# Sheet1.net
KiCad netlist of a schematic drawn in Altium Designer
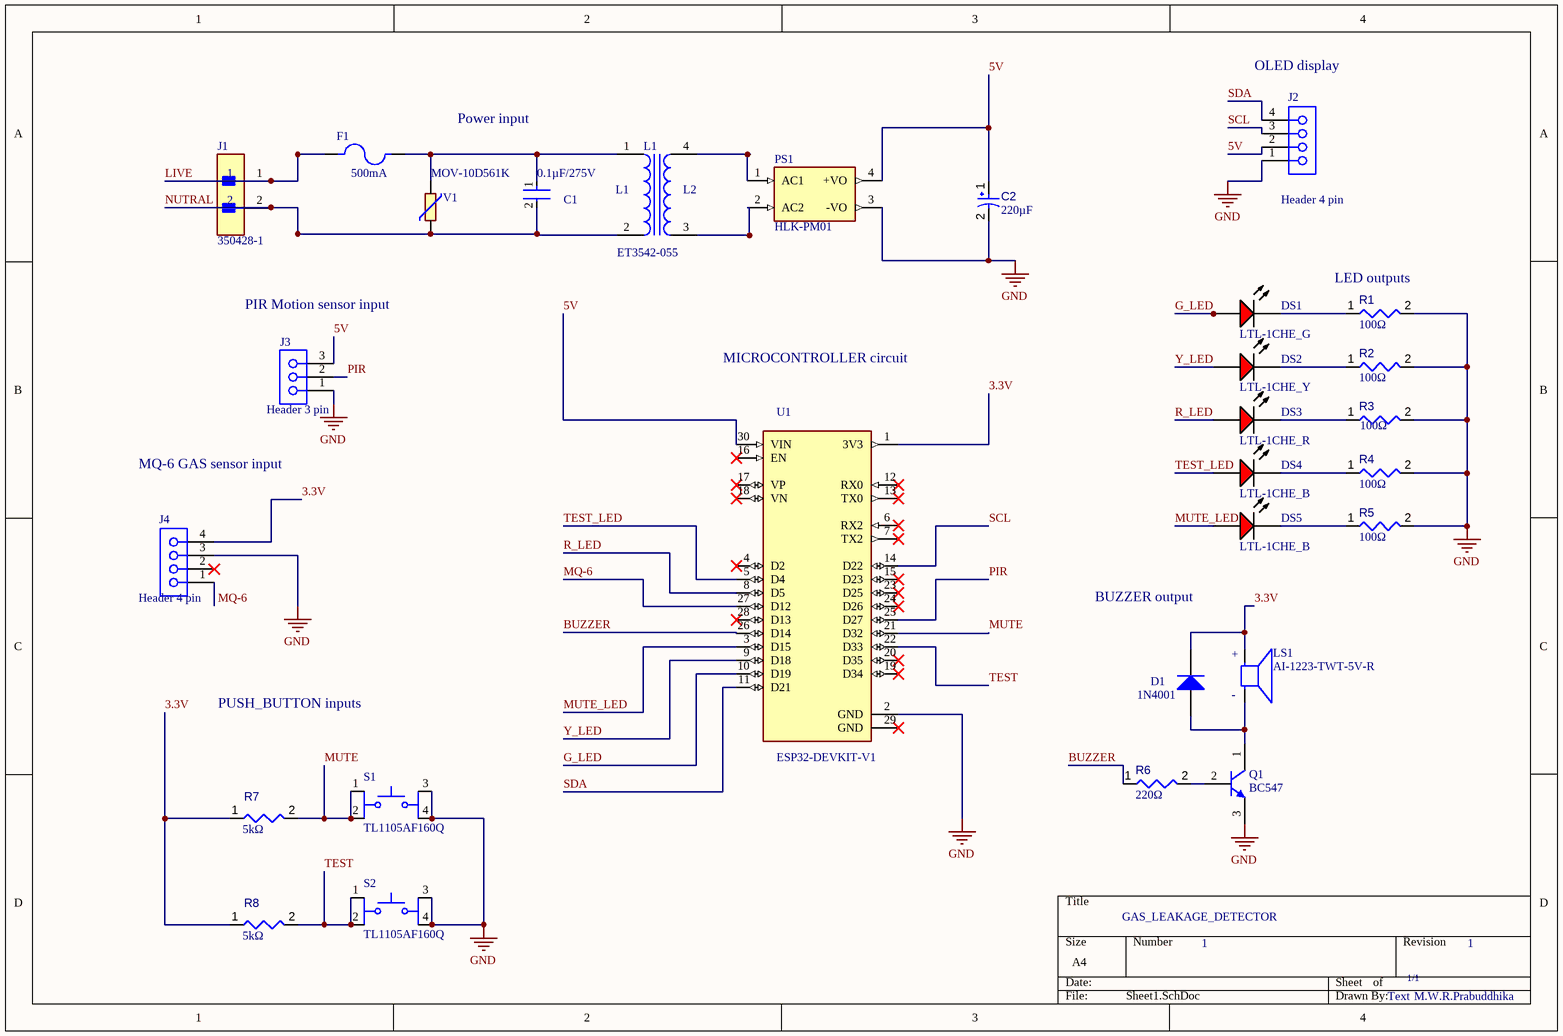
[diagram p0: Sheet1.SchDoc]

(export (version "E")
  (design (tool "Eeschema 10.0.6"))
  (components
    (comp (ref "C1")
      (value "0.1µF/275V")
      (footprint "FP-PMR209MC6100M100R30-MFG")
      (description "FILTER RC 100 OHM/0.1UF TH")
      (fields (field (name "VOLTAGE") "630V") (field (name "TOLERANCE") "20%"))
      (libsource (lib "Altium Content Vault") (part "b4654b650e69147ec39a6b967a45e02"))
    )
    (comp (ref "C2")
      (value "220µF")
      (footprint "CAPPR65-500-1250X1000X1350")
      (description "Aluminum Electrolytic Capacitor, 220 uF, +/- 20%, 50 V, -40 to 85 degC, 2-Pin THD, RoHS, Bulk")
      (fields (field (name "MANUFACTURER") "Panasonic") (field (name "TOLERANCE") "20%"))
      (libsource (lib "University of Moratuwa") (part "CAP-P-2"))
    )
    (comp (ref "D1")
      (value "1N4001")
      (footprint "FAIR-DO-41-2")
      (description "General Purpose Rectifier, 1.1 V, 1.0 A, -55 to 175 degC, 2-Pin DO-41, RoHS, Tape and Reel")
      (fields (field (name "MANUFACTURER") "Fairchild"))
      (libsource (lib "University of Moratuwa") (part "KESE-D_K1A2-2"))
    )
    (comp (ref "DS1")
      (value "LTL-1CHE_G")
      (footprint "INDPR60-254-520X380X650")
      (description "LED Uni-Color Red, 100 mW, 30 mA, -55 to 100 degC, 2-Pin THD, RoHS, Bulk")
      (fields (field (name "MANUFACTURER") "Lite-On"))
      (libsource (lib "University of Moratuwa") (part "LED-RED-AK-2"))
    )
    (comp (ref "DS2")
      (value "LTL-1CHE_Y")
      (footprint "INDPR60-254-520X380X650")
      (description "LED Uni-Color Red, 100 mW, 30 mA, -55 to 100 degC, 2-Pin THD, RoHS, Bulk")
      (fields (field (name "MANUFACTURER") "Lite-On"))
      (libsource (lib "University of Moratuwa") (part "LED-RED-AK-2"))
    )
    (comp (ref "DS3")
      (value "LTL-1CHE_R")
      (footprint "INDPR60-254-520X380X650")
      (description "LED Uni-Color Red, 100 mW, 30 mA, -55 to 100 degC, 2-Pin THD, RoHS, Bulk")
      (fields (field (name "MANUFACTURER") "Lite-On"))
      (libsource (lib "University of Moratuwa") (part "LED-RED-AK-2"))
    )
    (comp (ref "DS4")
      (value "LTL-1CHE_B")
      (footprint "INDPR60-254-520X380X650")
      (description "LED Uni-Color Red, 100 mW, 30 mA, -55 to 100 degC, 2-Pin THD, RoHS, Bulk")
      (fields (field (name "MANUFACTURER") "Lite-On"))
      (libsource (lib "University of Moratuwa") (part "LED-RED-AK-2"))
    )
    (comp (ref "DS5")
      (value "LTL-1CHE_B")
      (footprint "INDPR60-254-520X380X650")
      (description "LED Uni-Color Red, 100 mW, 30 mA, -55 to 100 degC, 2-Pin THD, RoHS, Bulk")
      (fields (field (name "MANUFACTURER") "Lite-On"))
      (libsource (lib "University of Moratuwa") (part "LED-RED-AK-2"))
    )
    (comp (ref "F1")
      (value "500mA")
      (footprint "FUSE_4628")
      (description "5mm Slim Line Fuse holder")
      (fields (field (name "MF") "Keystone") (field (name "MP") "4628"))
      (libsource (lib "University of Moratuwa") (part "4628"))
    )
    (comp (ref "J1")
      (value "350428-1")
      (footprint "FP-350428-1-MFG")
      (description "CONN HEADER VERT 2POS 6.35MM")
      (fields
        (field (name "OCTOPART") "https://octopart.com/350428-1-te+connectivity-46505355")
        (field (name "MANUFACTURER") "TE Connectivity")
      )
      (libsource (lib "Altium Content Vault") (part "3bc925449376181038e59eaffc5286c"))
    )
    (comp (ref "J2")
      (value "OLED display")
      (footprint "SMTC-SLW-104-01-X-S")
      (fields (field (name "MANUFACTURER") "Samtec") (field (name "PARTNUMBER") "SLW-104-01-G-S"))
      (libsource (lib "Altium Content Vault") (part "SMTC-SLW-104-01-X-S"))
    )
    (comp (ref "J3")
      (value "Header 3 pin")
      (footprint "SMTC-SLW-103-01-X-S")
      (fields (field (name "MANUFACTURER") "Samtec") (field (name "PARTNUMBER") "SLW-103-01-G-S"))
      (libsource (lib "Altium Content Vault") (part "SMTC-SLW-103-01-X-S"))
    )
    (comp (ref "J4")
      (value "MQ-6 GAS sensor input")
      (footprint "SMTC-SLW-104-01-X-S")
      (fields (field (name "MANUFACTURER") "Samtec") (field (name "PARTNUMBER") "SLW-104-01-G-S"))
      (libsource (lib "Altium Content Vault") (part "SMTC-SLW-104-01-X-S"))
    )
    (comp (ref "L1")
      (value "ET3542-055")
      (footprint "IND_ET3542-055")
      (description "COMMON MODE CHOKE 10.0mH@2.7Arms")
      (fields (field (name "MF") "Triad Magnetics"))
      (libsource (lib "University of Moratuwa") (part "ET3542-055"))
    )
    (comp (ref "LS1")
      (value "AI-1223-TWT-5V-R")
      (footprint "XDCR_AI-1223-TWT-5V-R")
      (description "ELECTRO MECHANICAL AUDIO INDICATOR")
      (fields (field (name "MF") "PUI Audio,"))
      (libsource (lib "AI-1223-TWT-5V-R") (part "AI-1223-TWT-5V-R"))
    )
    (comp (ref "PS1")
      (value "HLK-PM01")
      (footprint "CONV_HLK-PM01")
      (fields (field (name "MP") "hlk-pm01") (field (name "MF") "Hi-link"))
      (libsource (lib "University of Moratuwa") (part "HLK-PM01"))
    )
    (comp (ref "Q1")
      (value "BC547")
      (footprint "ONSC-TO-92-3-29-11_AM_BL")
      (description "Amplifier Transistor, NPN Silicon, 3-Pin TO-92, Pb-Free, Tape and Reel")
      (fields (field (name "MANUFACTURER") "On Semiconductor") (field (name "PARTNUMBER") "BC547BRL1G"))
      (libsource (lib "Altium Content Vault") (part "ONSC-NPN-C1B2E3-3"))
    )
    (comp (ref "R1")
      (value "100Ω")
      (footprint "RESA60-630X240")
      (description "Axial Resistor, 1 KOhm, +/- 1%, 250 mW, -55 to 155 degC, 2-Pin THD, RoHS, Bulk")
      (fields (field (name "TOLERANCE") "1%") (field (name "POWER") "250mW"))
      (libsource (lib "University of Moratuwa") (part "RES-2"))
    )
    (comp (ref "R2")
      (value "100Ω")
      (footprint "RESA60-630X240")
      (description "Axial Resistor, 1 KOhm, +/- 1%, 250 mW, -55 to 155 degC, 2-Pin THD, RoHS, Bulk")
      (fields (field (name "TOLERANCE") "1%") (field (name "POWER") "250mW"))
      (libsource (lib "University of Moratuwa") (part "RES-2"))
    )
    (comp (ref "R3")
      (value "100Ω")
      (footprint "RESA60-630X240")
      (description "Axial Resistor, 1 KOhm, +/- 1%, 250 mW, -55 to 155 degC, 2-Pin THD, RoHS, Bulk")
      (fields (field (name "TOLERANCE") "1%") (field (name "POWER") "250mW"))
      (libsource (lib "University of Moratuwa") (part "RES-2"))
    )
    (comp (ref "R4")
      (value "100Ω")
      (footprint "RESA60-630X240")
      (description "Axial Resistor, 1 KOhm, +/- 1%, 250 mW, -55 to 155 degC, 2-Pin THD, RoHS, Bulk")
      (fields (field (name "TOLERANCE") "1%") (field (name "POWER") "250mW"))
      (libsource (lib "University of Moratuwa") (part "RES-2"))
    )
    (comp (ref "R5")
      (value "100Ω")
      (footprint "RESA60-630X240")
      (description "Axial Resistor, 1 KOhm, +/- 1%, 250 mW, -55 to 155 degC, 2-Pin THD, RoHS, Bulk")
      (fields (field (name "TOLERANCE") "1%") (field (name "POWER") "250mW"))
      (libsource (lib "University of Moratuwa") (part "RES-2"))
    )
    (comp (ref "R6")
      (value "220Ω")
      (footprint "RESA60-630X240")
      (description "Axial Resistor, 1 KOhm, +/- 1%, 250 mW, -55 to 155 degC, 2-Pin THD, RoHS, Bulk")
      (fields (field (name "TOLERANCE") "1%") (field (name "POWER") "250mW"))
      (libsource (lib "University of Moratuwa") (part "RES-2"))
    )
    (comp (ref "R7")
      (value "5kΩ")
      (footprint "RESA60-630X240")
      (description "Axial Resistor, 1 KOhm, +/- 1%, 250 mW, -55 to 155 degC, 2-Pin THD, RoHS, Bulk")
      (fields (field (name "TOLERANCE") "1%") (field (name "POWER") "250mW"))
      (libsource (lib "University of Moratuwa") (part "RES-2"))
    )
    (comp (ref "R8")
      (value "5kΩ")
      (footprint "RESA60-630X240")
      (description "Axial Resistor, 1 KOhm, +/- 1%, 250 mW, -55 to 155 degC, 2-Pin THD, RoHS, Bulk")
      (fields (field (name "TOLERANCE") "1%") (field (name "POWER") "250mW"))
      (libsource (lib "University of Moratuwa") (part "RES-2"))
    )
    (comp (ref "S1")
      (value "TL1105AF160Q")
      (footprint "SW_TL1105AF160Q")
      (libsource (lib "University of Moratuwa") (part "TL1105AF160Q"))
    )
    (comp (ref "S2")
      (value "TL1105AF160Q")
      (footprint "SW_TL1105AF160Q")
      (libsource (lib "University of Moratuwa") (part "TL1105AF160Q"))
    )
    (comp (ref "U1")
      (value "ESP32-DEVKIT-V1")
      (footprint "MODULE_ESP32_DEVKIT_V1")
      (fields (field (name "MF") "Do it"))
      (libsource (lib "ESP32-DEVKIT-V1") (part "ESP32-DEVKIT-V1"))
    )
    (comp (ref "V1")
      (value "MOV-10D561K")
      (footprint "MOV-10D561")
      (description "560 V 2.5 kA Varistor 1 Circuit Through Hole Disc 10mm")
      (fields (field (name "MF") "Bourns"))
      (libsource (lib "University of Moratuwa") (part "MOV-10D561K"))
    )
  )
  (nets
    (net (code "1") (name "/3.3V") (class "Default")
      (node (ref "D1") (pin "1") (pinfunction "K_1") (pintype "passive"))
      (node (ref "J4") (pin "4") (pinfunction "4_4") (pintype "passive"))
      (node (ref "LS1") (pin "P") (pinfunction "POS_P") (pintype "passive"))
      (node (ref "R7") (pin "1") (pinfunction "1_1") (pintype "passive"))
      (node (ref "R8") (pin "1") (pinfunction "1_1") (pintype "passive"))
      (node (ref "U1") (pin "1") (pinfunction "3V3_1") (pintype "output"))
    )
    (net (code "2") (name "/5V") (class "Default")
      (node (ref "C2") (pin "1") (pinfunction "1_1") (pintype "passive"))
      (node (ref "J2") (pin "2") (pinfunction "2_2") (pintype "passive"))
      (node (ref "J3") (pin "3") (pinfunction "3_3") (pintype "passive"))
      (node (ref "PS1") (pin "4") (pinfunction "+VO_4") (pintype "output"))
      (node (ref "U1") (pin "30") (pinfunction "VIN_30") (pintype "input"))
    )
    (net (code "3") (name "/BUZZER") (class "Default")
      (node (ref "R6") (pin "1") (pinfunction "1_1") (pintype "passive"))
      (node (ref "U1") (pin "26") (pinfunction "D14_26") (pintype "bidirectional"))
    )
    (net (code "4") (name "/G_LED") (class "Default")
      (node (ref "DS1") (pin "1") (pinfunction "A_1") (pintype "passive"))
      (node (ref "U1") (pin "10") (pinfunction "D19_10") (pintype "bidirectional"))
    )
    (net (code "5") (name "/LIVE") (class "Default")
      (node (ref "F1") (pin "1") (pinfunction "1_1") (pintype "passive"))
      (node (ref "J1") (pin "1") (pinfunction "1_1") (pintype "passive"))
    )
    (net (code "6") (name "/MQ-6") (class "Default")
      (node (ref "U1") (pin "27") (pinfunction "D12_27") (pintype "bidirectional"))
    )
    (net (code "7") (name "/MUTE") (class "Default")
      (node (ref "R7") (pin "2") (pinfunction "2_2") (pintype "passive"))
      (node (ref "S1") (pin "1") (pinfunction "1_1") (pintype "passive"))
      (node (ref "S1") (pin "2") (pinfunction "2_2") (pintype "passive"))
      (node (ref "U1") (pin "21") (pinfunction "D32_21") (pintype "bidirectional"))
    )
    (net (code "8") (name "/MUTE_LED") (class "Default")
      (node (ref "DS5") (pin "1") (pinfunction "A_1") (pintype "passive"))
      (node (ref "U1") (pin "3") (pinfunction "D15_3") (pintype "bidirectional"))
    )
    (net (code "9") (name "/NUTRAL") (class "Default")
      (node (ref "C1") (pin "2") (pinfunction "2_2") (pintype "passive"))
      (node (ref "J1") (pin "2") (pinfunction "2_2") (pintype "passive"))
      (node (ref "L1") (pin "2") (pinfunction "2_2") (pintype "passive"))
      (node (ref "V1") (pin "2") (pinfunction "2_2") (pintype "passive"))
    )
    (net (code "10") (name "/PIR") (class "Default")
      (node (ref "J3") (pin "2") (pinfunction "2_2") (pintype "passive"))
      (node (ref "U1") (pin "25") (pinfunction "D27_25") (pintype "bidirectional"))
    )
    (net (code "11") (name "/R_LED") (class "Default")
      (node (ref "DS3") (pin "1") (pinfunction "A_1") (pintype "passive"))
      (node (ref "U1") (pin "8") (pinfunction "D5_8") (pintype "bidirectional"))
    )
    (net (code "12") (name "/SCL") (class "Default")
      (node (ref "J2") (pin "3") (pinfunction "3_3") (pintype "passive"))
      (node (ref "U1") (pin "14") (pinfunction "D22_14") (pintype "bidirectional"))
    )
    (net (code "13") (name "/SDA") (class "Default")
      (node (ref "J2") (pin "4") (pinfunction "4_4") (pintype "passive"))
      (node (ref "U1") (pin "11") (pinfunction "D21_11") (pintype "bidirectional"))
    )
    (net (code "14") (name "/TEST") (class "Default")
      (node (ref "R8") (pin "2") (pinfunction "2_2") (pintype "passive"))
      (node (ref "S2") (pin "1") (pinfunction "1_1") (pintype "passive"))
      (node (ref "S2") (pin "2") (pinfunction "2_2") (pintype "passive"))
      (node (ref "U1") (pin "22") (pinfunction "D33_22") (pintype "bidirectional"))
    )
    (net (code "15") (name "/TEST_LED") (class "Default")
      (node (ref "DS4") (pin "1") (pinfunction "A_1") (pintype "passive"))
      (node (ref "U1") (pin "5") (pinfunction "D4_5") (pintype "bidirectional"))
    )
    (net (code "16") (name "/Y_LED") (class "Default")
      (node (ref "DS2") (pin "1") (pinfunction "A_1") (pintype "passive"))
      (node (ref "U1") (pin "9") (pinfunction "D18_9") (pintype "bidirectional"))
    )
    (net (code "17") (name "GND") (class "Default")
      (node (ref "C2") (pin "2") (pinfunction "2_2") (pintype "passive"))
      (node (ref "J2") (pin "1") (pinfunction "1_1") (pintype "passive"))
      (node (ref "J3") (pin "1") (pinfunction "1_1") (pintype "passive"))
      (node (ref "J4") (pin "3") (pinfunction "3_3") (pintype "passive"))
      (node (ref "PS1") (pin "3") (pinfunction "-VO_3") (pintype "output"))
      (node (ref "Q1") (pin "3") (pinfunction "E_3") (pintype "passive"))
      (node (ref "R1") (pin "2") (pinfunction "2_2") (pintype "passive"))
      (node (ref "R2") (pin "2") (pinfunction "2_2") (pintype "passive"))
      (node (ref "R3") (pin "2") (pinfunction "2_2") (pintype "passive"))
      (node (ref "R4") (pin "2") (pinfunction "2_2") (pintype "passive"))
      (node (ref "R5") (pin "2") (pinfunction "2_2") (pintype "passive"))
      (node (ref "S1") (pin "3") (pinfunction "3_3") (pintype "passive"))
      (node (ref "S1") (pin "4") (pinfunction "4_4") (pintype "passive"))
      (node (ref "S2") (pin "3") (pinfunction "3_3") (pintype "passive"))
      (node (ref "S2") (pin "4") (pinfunction "4_4") (pintype "passive"))
      (node (ref "U1") (pin "2") (pinfunction "GND_2") (pintype "power_in"))
    )
    (net (code "18") (name "Net-(C1-Pad1)") (class "Default")
      (node (ref "C1") (pin "1") (pinfunction "1_1") (pintype "passive"))
      (node (ref "F1") (pin "2") (pinfunction "2_2") (pintype "passive"))
      (node (ref "L1") (pin "1") (pinfunction "1_1") (pintype "passive"))
      (node (ref "V1") (pin "1") (pinfunction "1_1") (pintype "passive"))
    )
    (net (code "19") (name "Net-(D1-A)") (class "Default")
      (node (ref "D1") (pin "2") (pinfunction "A_2") (pintype "passive"))
      (node (ref "LS1") (pin "N") (pinfunction "NEG_N") (pintype "passive"))
      (node (ref "Q1") (pin "1") (pinfunction "C_1") (pintype "passive"))
    )
    (net (code "20") (name "Net-(DS1-K)") (class "Default")
      (node (ref "DS1") (pin "2") (pinfunction "K_2") (pintype "passive"))
      (node (ref "R1") (pin "1") (pinfunction "1_1") (pintype "passive"))
    )
    (net (code "21") (name "Net-(DS2-K)") (class "Default")
      (node (ref "DS2") (pin "2") (pinfunction "K_2") (pintype "passive"))
      (node (ref "R2") (pin "1") (pinfunction "1_1") (pintype "passive"))
    )
    (net (code "22") (name "Net-(DS3-K)") (class "Default")
      (node (ref "DS3") (pin "2") (pinfunction "K_2") (pintype "passive"))
      (node (ref "R3") (pin "1") (pinfunction "1_1") (pintype "passive"))
    )
    (net (code "23") (name "Net-(DS4-K)") (class "Default")
      (node (ref "DS4") (pin "2") (pinfunction "K_2") (pintype "passive"))
      (node (ref "R4") (pin "1") (pinfunction "1_1") (pintype "passive"))
    )
    (net (code "24") (name "Net-(DS5-K)") (class "Default")
      (node (ref "DS5") (pin "2") (pinfunction "K_2") (pintype "passive"))
      (node (ref "R5") (pin "1") (pinfunction "1_1") (pintype "passive"))
    )
    (net (code "25") (name "Net-(PS1-AC1)") (class "Default")
      (node (ref "L1") (pin "4") (pinfunction "4_4") (pintype "passive"))
      (node (ref "PS1") (pin "1") (pinfunction "AC1_1") (pintype "input"))
    )
    (net (code "26") (name "Net-(PS1-AC2)") (class "Default")
      (node (ref "L1") (pin "3") (pinfunction "3_3") (pintype "passive"))
      (node (ref "PS1") (pin "2") (pinfunction "AC2_2") (pintype "input"))
    )
    (net (code "27") (name "Net-(Q1-B)") (class "Default")
      (node (ref "Q1") (pin "2") (pinfunction "B_2") (pintype "passive"))
      (node (ref "R6") (pin "2") (pinfunction "2_2") (pintype "passive"))
    )
    (net (code "28") (name "unconnected-(J4-Pad1)") (class "Default")
      (node (ref "J4") (pin "1") (pinfunction "1_1") (pintype "passive"))
    )
    (net (code "29") (name "unconnected-(J4-Pad2)") (class "Default")
      (node (ref "J4") (pin "2") (pinfunction "2_2") (pintype "passive+no_connect"))
    )
    (net (code "30") (name "unconnected-(U1-D2-Pad4)") (class "Default")
      (node (ref "U1") (pin "4") (pinfunction "D2_4") (pintype "bidirectional+no_connect"))
    )
    (net (code "31") (name "unconnected-(U1-D13-Pad28)") (class "Default")
      (node (ref "U1") (pin "28") (pinfunction "D13_28") (pintype "bidirectional+no_connect"))
    )
    (net (code "32") (name "unconnected-(U1-D23-Pad15)") (class "Default")
      (node (ref "U1") (pin "15") (pinfunction "D23_15") (pintype "bidirectional+no_connect"))
    )
    (net (code "33") (name "unconnected-(U1-D25-Pad23)") (class "Default")
      (node (ref "U1") (pin "23") (pinfunction "D25_23") (pintype "bidirectional+no_connect"))
    )
    (net (code "34") (name "unconnected-(U1-D26-Pad24)") (class "Default")
      (node (ref "U1") (pin "24") (pinfunction "D26_24") (pintype "bidirectional+no_connect"))
    )
    (net (code "35") (name "unconnected-(U1-D34-Pad19)") (class "Default")
      (node (ref "U1") (pin "19") (pinfunction "D34_19") (pintype "bidirectional+no_connect"))
    )
    (net (code "36") (name "unconnected-(U1-D35-Pad20)") (class "Default")
      (node (ref "U1") (pin "20") (pinfunction "D35_20") (pintype "bidirectional+no_connect"))
    )
    (net (code "37") (name "unconnected-(U1-EN-Pad16)") (class "Default")
      (node (ref "U1") (pin "16") (pinfunction "EN_16") (pintype "input+no_connect"))
    )
    (net (code "38") (name "unconnected-(U1-GND-Pad29)") (class "Default")
      (node (ref "U1") (pin "29") (pinfunction "GND_29") (pintype "power_in+no_connect"))
    )
    (net (code "39") (name "unconnected-(U1-RX0-Pad12)") (class "Default")
      (node (ref "U1") (pin "12") (pinfunction "RX0_12") (pintype "input+no_connect"))
    )
    (net (code "40") (name "unconnected-(U1-RX2-Pad6)") (class "Default")
      (node (ref "U1") (pin "6") (pinfunction "RX2_6") (pintype "input+no_connect"))
    )
    (net (code "41") (name "unconnected-(U1-TX0-Pad13)") (class "Default")
      (node (ref "U1") (pin "13") (pinfunction "TX0_13") (pintype "output+no_connect"))
    )
    (net (code "42") (name "unconnected-(U1-TX2-Pad7)") (class "Default")
      (node (ref "U1") (pin "7") (pinfunction "TX2_7") (pintype "output+no_connect"))
    )
    (net (code "43") (name "unconnected-(U1-VN-Pad18)") (class "Default")
      (node (ref "U1") (pin "18") (pinfunction "VN_18") (pintype "bidirectional+no_connect"))
    )
    (net (code "44") (name "unconnected-(U1-VP-Pad17)") (class "Default")
      (node (ref "U1") (pin "17") (pinfunction "VP_17") (pintype "bidirectional+no_connect"))
    )
  )
)
